# Payloadv04.net
KiCad netlist of a schematic drawn in EAGLE
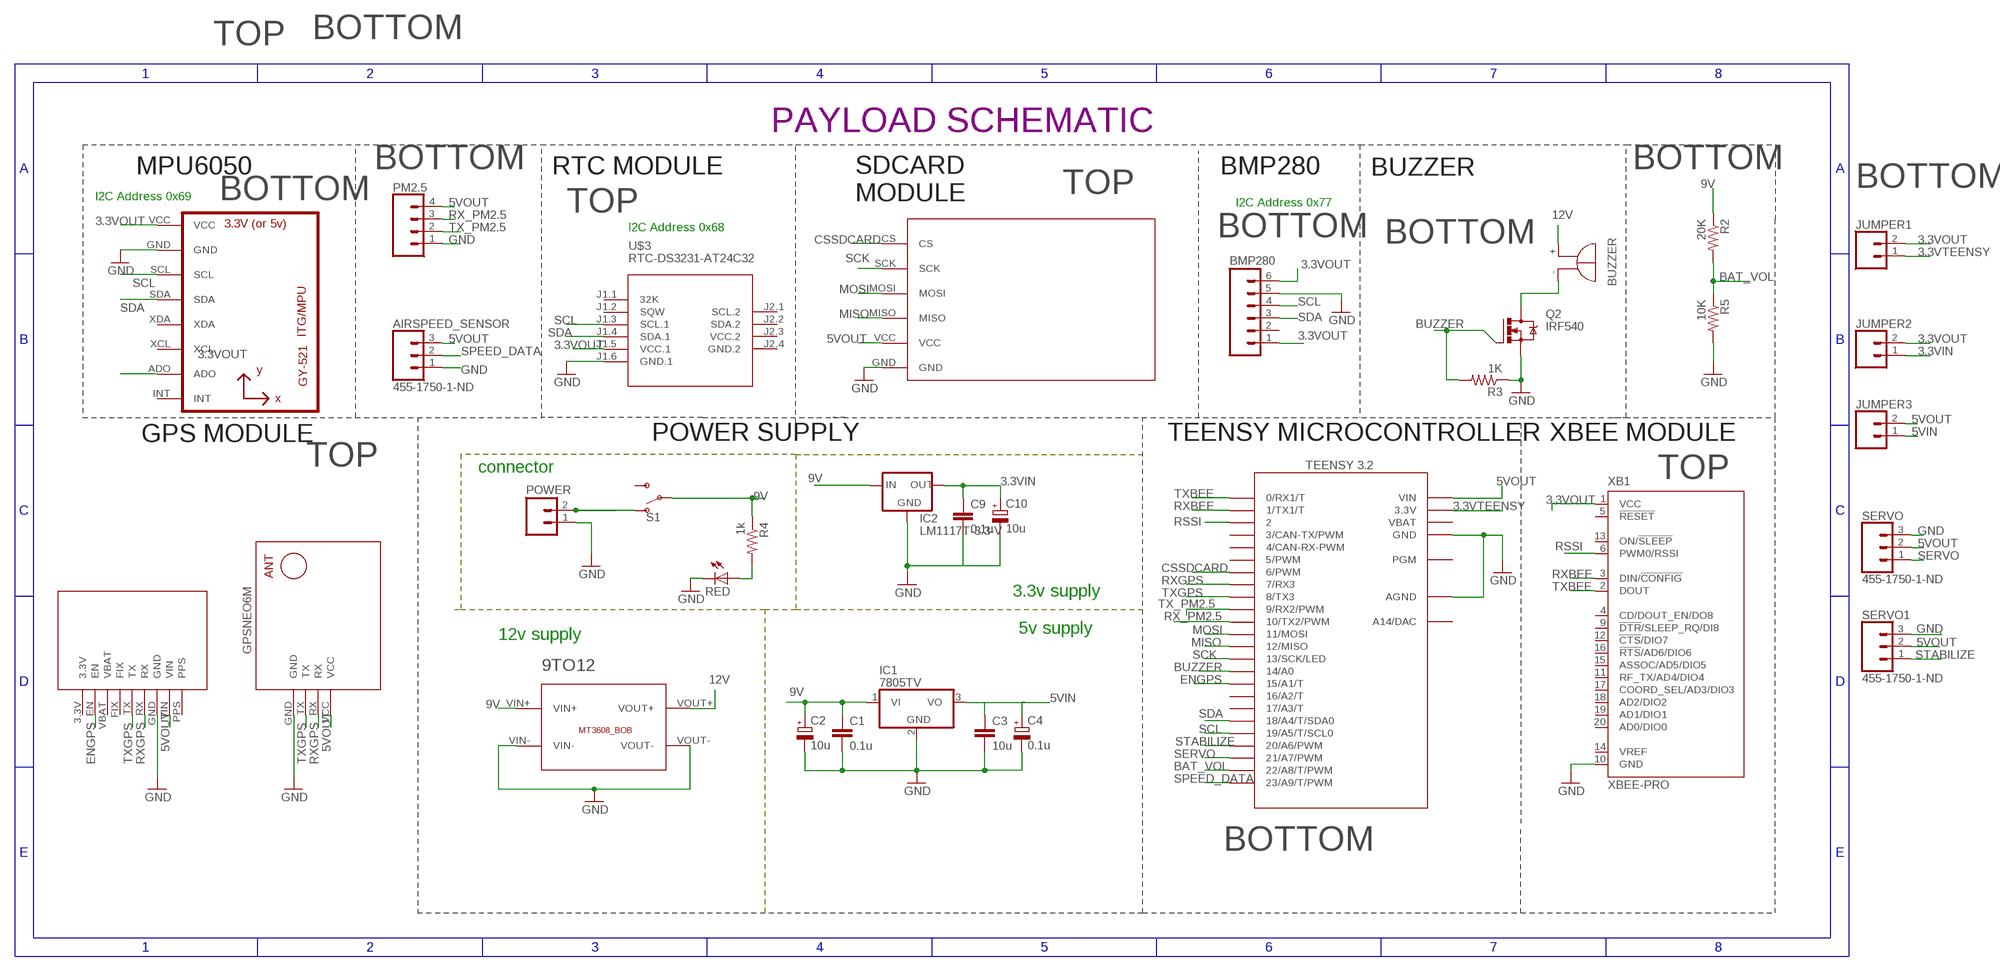
[diagram p0: schematic, sheet 1]

(export (version "E")
  (design (tool "Eeschema 10.0.6"))
  (components
    (comp (ref "9TO12")
      (value "BREAKOUTS_MT3608_BOB")
      (footprint "eagle-import:BREAKOUTS_MT3608_BOB")
      (libsource (lib "eagle-import") (part "BREAKOUTS_MT3608_BOB"))
    )
    (comp (ref "AIRSPEED_SENSOR")
      (value "455-1750-1-ND")
      (footprint "eagle-import:1X03")
      (libsource (lib "eagle-import") (part "CONN_03"))
    )
    (comp (ref "BMP280")
      (value "M06")
      (footprint "eagle-import:06P")
      (libsource (lib "eagle-import") (part "M06"))
    )
    (comp (ref "C1")
      (value "0.1u")
      (footprint "eagle-import:C025-025X050")
      (libsource (lib "eagle-import") (part "C-EU025-025X050"))
    )
    (comp (ref "C2")
      (value "10u")
      (footprint "eagle-import:E2,5-6")
      (libsource (lib "eagle-import") (part "CPOL-EUE2.5-6"))
    )
    (comp (ref "C3")
      (value "10u")
      (footprint "eagle-import:C025-025X050")
      (libsource (lib "eagle-import") (part "C-EU025-025X050"))
    )
    (comp (ref "C4")
      (value "0.1u")
      (footprint "eagle-import:E2,5-6")
      (libsource (lib "eagle-import") (part "CPOL-EUE2.5-6"))
    )
    (comp (ref "C9")
      (value "0.1u")
      (footprint "eagle-import:C025-025X050")
      (libsource (lib "eagle-import") (part "C-EU025-025X050"))
    )
    (comp (ref "C10")
      (value "10u")
      (footprint "eagle-import:E2,5-6")
      (libsource (lib "eagle-import") (part "CPOL-EUE2.5-6"))
    )
    (comp (ref "IC1")
      (value "7805TV")
      (footprint "eagle-import:TO220V")
      (libsource (lib "eagle-import") (part "78TV05"))
    )
    (comp (ref "IC2")
      (value "LM1117T-3.3-V")
      (footprint "eagle-import:TO220V")
      (libsource (lib "eagle-import") (part "LM1117T--V3.3"))
    )
    (comp (ref "JUMPER1")
      (value "CONN_02")
      (footprint "eagle-import:1X02")
      (libsource (lib "eagle-import") (part "CONN_02"))
    )
    (comp (ref "JUMPER2")
      (value "CONN_02")
      (footprint "eagle-import:1X02")
      (libsource (lib "eagle-import") (part "CONN_02"))
    )
    (comp (ref "JUMPER3")
      (value "CONN_02")
      (footprint "eagle-import:1X02")
      (libsource (lib "eagle-import") (part "CONN_02"))
    )
    (comp (ref "PM2.5")
      (value "CONN_04")
      (footprint "eagle-import:1X04")
      (libsource (lib "eagle-import") (part "CONN_04"))
    )
    (comp (ref "POWER")
      (value "CEDT_JANUARY_2015_V5_M02")
      (footprint "eagle-import:CEDT_JANUARY_2015_V5_02P")
      (libsource (lib "eagle-import") (part "CEDT_JANUARY_2015_V5_M02"))
    )
    (comp (ref "Q2")
      (value "IRF540")
      (footprint "eagle-import:TO220BV")
      (libsource (lib "eagle-import") (part "IRF540"))
    )
    (comp (ref "R2")
      (value "20K")
      (footprint "eagle-import:0204_7")
      (libsource (lib "eagle-import") (part "R-US_0204/7"))
    )
    (comp (ref "R3")
      (value "1K")
      (footprint "eagle-import:0204_7")
      (libsource (lib "eagle-import") (part "R-US_0204/7"))
    )
    (comp (ref "R4")
      (value "1k")
      (footprint "eagle-import:0204_7")
      (libsource (lib "eagle-import") (part "R-US_0204/7"))
    )
    (comp (ref "R5")
      (value "10K")
      (footprint "eagle-import:0204_7")
      (libsource (lib "eagle-import") (part "R-US_0204/7"))
    )
    (comp (ref "RED")
      (value "red")
      (footprint "eagle-import:LED3MM")
      (libsource (lib "eagle-import") (part "LED3MM"))
    )
    (comp (ref "S1")
      (value "SWITCH-SPDT-PTH-11.6X4.0MM")
      (footprint "eagle-import:SWITCH_SPDT_PTH_11.6X4.0MM")
      (libsource (lib "eagle-import") (part "SWITCH-SPDT-PTH-11.6X4.0MM"))
    )
    (comp (ref "SERVO")
      (value "455-1750-1-ND")
      (footprint "eagle-import:1X03")
      (libsource (lib "eagle-import") (part "CONN_03"))
    )
    (comp (ref "SERVO1")
      (value "455-1750-1-ND")
      (footprint "eagle-import:1X03")
      (libsource (lib "eagle-import") (part "CONN_03"))
    )
    (comp (ref "SG1")
      (value "BUZZER_EB2209A")
      (footprint "eagle-import:BUZZER_EB2209A")
      (libsource (lib "eagle-import") (part "BUZZER_EB2209A"))
    )
    (comp (ref "U$1")
      (value "GPS-RECEIVER-NEO6M")
      (footprint "eagle-import:GPS-RECEIVER-NEO6M")
      (libsource (lib "eagle-import") (part "GPS-RECEIVER-NEO6M"))
    )
    (comp (ref "U$2")
      (value "TEENSY_3.1-3.2_OUTER_ROW")
      (footprint "eagle-import:TEENSY_3.0-3.2&LC_OUTER_ROW")
      (libsource (lib "eagle-import") (part "TEENSY_3.1-3.2_OUTER_ROW"))
    )
    (comp (ref "U$3")
      (value "RTC-DS3231-AT24C32")
      (footprint "eagle-import:RTC-DS3231-AT24C32")
      (libsource (lib "eagle-import") (part "RTC-DS3231-AT24C32"))
    )
    (comp (ref "U$4")
      (value "ADAFRUIT_GPS")
      (footprint "eagle-import:ADAFRUIT_GPS")
      (libsource (lib "eagle-import") (part "ADAFRUIT_GPS"))
    )
    (comp (ref "U$5")
      (value "SDCARD")
      (footprint "eagle-import:M0SDCARDMODULE")
      (libsource (lib "eagle-import") (part "SDCARD"))
    )
    (comp (ref "U1")
      (value "GY-521MPU6050")
      (footprint "eagle-import:GY-521")
      (libsource (lib "eagle-import") (part "GY-521MPU6050"))
    )
    (comp (ref "XB1")
      (value "XBEE-PRO")
      (footprint "eagle-import:XBEE-PRO")
      (fields (field (name "MPN") "XBP24-AWI-001"))
      (libsource (lib "eagle-import") (part "XBEE-PRO"))
    )
  )
  (nets
    (net (code "1") (name "/3.3VIN") (class "Default")
      (node (ref "C10") (pin "+") (pinfunction "+_+") (pintype "passive"))
      (node (ref "C9") (pin "1") (pinfunction "1_1") (pintype "passive"))
      (node (ref "IC2") (pin "2") (pinfunction "OUT_2") (pintype "passive"))
      (node (ref "JUMPER2") (pin "1") (pinfunction "1_1") (pintype "passive"))
    )
    (net (code "2") (name "/3.3VOUT") (class "Default")
      (node (ref "BMP280") (pin "1") (pinfunction "1_1") (pintype "passive"))
      (node (ref "BMP280") (pin "6") (pinfunction "6_6") (pintype "passive"))
      (node (ref "JUMPER1") (pin "2") (pinfunction "2_2") (pintype "passive"))
      (node (ref "JUMPER2") (pin "2") (pinfunction "2_2") (pintype "passive"))
      (node (ref "U$3") (pin "J1.5") (pinfunction "VCC.1_J1.5") (pintype "power_in"))
      (node (ref "U1") (pin "ADO") (pinfunction "ADO_ADO") (pintype "bidirectional"))
      (node (ref "U1") (pin "VCC") (pinfunction "VCC_VCC") (pintype "bidirectional"))
      (node (ref "XB1") (pin "1") (pinfunction "VCC_1") (pintype "power_in"))
    )
    (net (code "3") (name "/3.3VTEENSY") (class "Default")
      (node (ref "JUMPER1") (pin "1") (pinfunction "1_1") (pintype "passive"))
      (node (ref "U$2") (pin "3.3V") (pinfunction "3.3V_3.3V") (pintype "power_in"))
      (node (ref "U$2") (pin "3.3V1") (pinfunction "3.3V_3.3V1") (pintype "power_in"))
    )
    (net (code "4") (name "/5VIN") (class "Default")
      (node (ref "C3") (pin "1") (pinfunction "1_1") (pintype "passive"))
      (node (ref "C4") (pin "+") (pinfunction "+_+") (pintype "passive"))
      (node (ref "IC1") (pin "3") (pinfunction "VO_3") (pintype "passive"))
      (node (ref "JUMPER3") (pin "1") (pinfunction "1_1") (pintype "passive"))
    )
    (net (code "5") (name "/5VOUT") (class "Default")
      (node (ref "AIRSPEED_SENSOR") (pin "3") (pinfunction "3_3") (pintype "passive"))
      (node (ref "JUMPER3") (pin "2") (pinfunction "2_2") (pintype "passive"))
      (node (ref "PM2.5") (pin "4") (pinfunction "4_4") (pintype "passive"))
      (node (ref "SERVO") (pin "2") (pinfunction "2_2") (pintype "passive"))
      (node (ref "SERVO1") (pin "2") (pinfunction "2_2") (pintype "passive"))
      (node (ref "U$1") (pin "VCC") (pinfunction "VCC_VCC") (pintype "power_in"))
      (node (ref "U$2") (pin "VIN") (pinfunction "VIN_VIN") (pintype "power_in"))
      (node (ref "U$4") (pin "VIN") (pinfunction "VIN_VIN") (pintype "bidirectional"))
      (node (ref "U$5") (pin "VCC") (pinfunction "VCC_VCC") (pintype "bidirectional"))
    )
    (net (code "6") (name "/9V") (class "Default")
      (node (ref "9TO12") (pin "VIN+") (pinfunction "VIN+_VIN+") (pintype "bidirectional"))
      (node (ref "C1") (pin "1") (pinfunction "1_1") (pintype "passive"))
      (node (ref "C2") (pin "+") (pinfunction "+_+") (pintype "passive"))
      (node (ref "IC1") (pin "1") (pinfunction "VI_1") (pintype "input"))
      (node (ref "IC2") (pin "3") (pinfunction "IN_3") (pintype "input"))
      (node (ref "R2") (pin "1") (pinfunction "1_1") (pintype "passive"))
      (node (ref "R4") (pin "1") (pinfunction "1_1") (pintype "passive"))
      (node (ref "S1") (pin "2") (pinfunction "P_2") (pintype "passive"))
    )
    (net (code "7") (name "/12V") (class "Default")
      (node (ref "9TO12") (pin "VOUT+") (pinfunction "VOUT+_VOUT+") (pintype "bidirectional"))
      (node (ref "SG1") (pin "+") (pinfunction "+_+") (pintype "passive"))
    )
    (net (code "8") (name "/BAT_VOL") (class "Default")
      (node (ref "R2") (pin "2") (pinfunction "2_2") (pintype "passive"))
      (node (ref "R5") (pin "1") (pinfunction "1_1") (pintype "passive"))
      (node (ref "U$2") (pin "22/A8") (pinfunction "22/A8/T/PWM_22/A8") (pintype "bidirectional"))
    )
    (net (code "9") (name "/BUZZER") (class "Default")
      (node (ref "Q2") (pin "G") (pinfunction "G_G") (pintype "passive"))
      (node (ref "R3") (pin "2") (pinfunction "2_2") (pintype "passive"))
      (node (ref "U$2") (pin "14/A0") (pinfunction "14/A0_14/A0") (pintype "bidirectional"))
    )
    (net (code "10") (name "/CSSDCARD") (class "Default")
      (node (ref "U$2") (pin "6") (pinfunction "6/PWM_6") (pintype "bidirectional"))
      (node (ref "U$5") (pin "CS") (pinfunction "CS_CS") (pintype "bidirectional"))
    )
    (net (code "11") (name "/ENGPS") (class "Default")
      (node (ref "U$2") (pin "15/A1") (pinfunction "15/A1/T_15/A1") (pintype "bidirectional"))
      (node (ref "U$4") (pin "EN") (pinfunction "EN_EN") (pintype "bidirectional"))
    )
    (net (code "12") (name "/GND.2") (class "Default")
      (node (ref "U$3") (pin "J2.4") (pinfunction "GND.2_J2.4") (pintype "power_in"))
    )
    (net (code "13") (name "/MISO") (class "Default")
      (node (ref "U$2") (pin "12") (pinfunction "12/MISO_12") (pintype "bidirectional"))
      (node (ref "U$5") (pin "MISO") (pinfunction "MISO_MISO") (pintype "bidirectional"))
    )
    (net (code "14") (name "/MOSI") (class "Default")
      (node (ref "U$2") (pin "11") (pinfunction "11/MOSI_11") (pintype "bidirectional"))
      (node (ref "U$5") (pin "MOSI") (pinfunction "MOSI_MOSI") (pintype "bidirectional"))
    )
    (net (code "15") (name "/RSSI") (class "Default")
      (node (ref "U$2") (pin "2") (pinfunction "2_2") (pintype "bidirectional"))
      (node (ref "XB1") (pin "6") (pinfunction "PWM0/RSSI_6") (pintype "output"))
    )
    (net (code "16") (name "/RXBEE") (class "Default")
      (node (ref "U$2") (pin "1") (pinfunction "1/TX1/T_1") (pintype "bidirectional"))
      (node (ref "XB1") (pin "3") (pinfunction "DIN/~{CONFIG}_3") (pintype "input"))
    )
    (net (code "17") (name "/RXGPS") (class "Default")
      (node (ref "U$1") (pin "RX") (pinfunction "RX_RX") (pintype "bidirectional"))
      (node (ref "U$2") (pin "7") (pinfunction "7/RX3_7") (pintype "bidirectional"))
      (node (ref "U$4") (pin "RX") (pinfunction "RX_RX") (pintype "bidirectional"))
    )
    (net (code "18") (name "/RX_PM2.5") (class "Default")
      (node (ref "PM2.5") (pin "3") (pinfunction "3_3") (pintype "passive"))
      (node (ref "U$2") (pin "10") (pinfunction "10/TX2/PWM_10") (pintype "bidirectional"))
    )
    (net (code "19") (name "/SCK") (class "Default")
      (node (ref "U$2") (pin "13") (pinfunction "13/SCK/LED_13") (pintype "bidirectional"))
      (node (ref "U$5") (pin "SCK") (pinfunction "SCK_SCK") (pintype "bidirectional"))
    )
    (net (code "20") (name "/SCL") (class "Default")
      (node (ref "BMP280") (pin "4") (pinfunction "4_4") (pintype "passive"))
      (node (ref "U$2") (pin "19/A5") (pinfunction "19/A5/T/SCL0_19/A5") (pintype "bidirectional"))
      (node (ref "U$3") (pin "J1.3") (pinfunction "SCL.1_J1.3") (pintype "bidirectional"))
      (node (ref "U1") (pin "SCL") (pinfunction "SCL_SCL") (pintype "bidirectional"))
    )
    (net (code "21") (name "/SDA") (class "Default")
      (node (ref "BMP280") (pin "3") (pinfunction "3_3") (pintype "passive"))
      (node (ref "U$2") (pin "18/A4") (pinfunction "18/A4/T/SDA0_18/A4") (pintype "bidirectional"))
      (node (ref "U$3") (pin "J1.4") (pinfunction "SDA.1_J1.4") (pintype "bidirectional"))
      (node (ref "U1") (pin "SDA") (pinfunction "SDA_SDA") (pintype "bidirectional"))
    )
    (net (code "22") (name "/SERVO") (class "Default")
      (node (ref "SERVO") (pin "1") (pinfunction "1_1") (pintype "passive"))
      (node (ref "U$2") (pin "21/A7") (pinfunction "21/A7/PWM_21/A7") (pintype "bidirectional"))
    )
    (net (code "23") (name "/SPEED_DATA") (class "Default")
      (node (ref "AIRSPEED_SENSOR") (pin "2") (pinfunction "2_2") (pintype "passive"))
      (node (ref "U$2") (pin "23/A9") (pinfunction "23/A9/T/PWM_23/A9") (pintype "bidirectional"))
    )
    (net (code "24") (name "/STABILIZE") (class "Default")
      (node (ref "SERVO1") (pin "1") (pinfunction "1_1") (pintype "passive"))
      (node (ref "U$2") (pin "20/A6") (pinfunction "20/A6/PWM_20/A6") (pintype "bidirectional"))
    )
    (net (code "25") (name "/TXBEE") (class "Default")
      (node (ref "U$2") (pin "0") (pinfunction "0/RX1/T_0") (pintype "bidirectional"))
      (node (ref "XB1") (pin "2") (pinfunction "DOUT_2") (pintype "output"))
    )
    (net (code "26") (name "/TXGPS") (class "Default")
      (node (ref "U$1") (pin "TX") (pinfunction "TX_TX") (pintype "bidirectional"))
      (node (ref "U$2") (pin "8") (pinfunction "8/TX3_8") (pintype "bidirectional"))
      (node (ref "U$4") (pin "TX") (pinfunction "TX_TX") (pintype "bidirectional"))
    )
    (net (code "27") (name "/TX_PM2.5") (class "Default")
      (node (ref "PM2.5") (pin "2") (pinfunction "2_2") (pintype "passive"))
      (node (ref "U$2") (pin "9") (pinfunction "9/RX2/PWM_9") (pintype "bidirectional"))
    )
    (net (code "28") (name "/VBAT") (class "Default")
      (node (ref "U$2") (pin "VBAT") (pinfunction "VBAT_VBAT") (pintype "power_in"))
    )
    (net (code "29") (name "/VCC.2") (class "Default")
      (node (ref "U$3") (pin "J2.3") (pinfunction "VCC.2_J2.3") (pintype "power_in"))
    )
    (net (code "30") (name "GND") (class "Default")
      (node (ref "9TO12") (pin "VIN-") (pinfunction "VIN-_VIN-") (pintype "bidirectional"))
      (node (ref "9TO12") (pin "VOUT-") (pinfunction "VOUT-_VOUT-") (pintype "bidirectional"))
      (node (ref "AIRSPEED_SENSOR") (pin "1") (pinfunction "1_1") (pintype "passive"))
      (node (ref "BMP280") (pin "5") (pinfunction "5_5") (pintype "passive"))
      (node (ref "C1") (pin "2") (pinfunction "2_2") (pintype "passive"))
      (node (ref "C10") (pin "-") (pinfunction "-_-") (pintype "passive"))
      (node (ref "C2") (pin "-") (pinfunction "-_-") (pintype "passive"))
      (node (ref "C3") (pin "2") (pinfunction "2_2") (pintype "passive"))
      (node (ref "C4") (pin "-") (pinfunction "-_-") (pintype "passive"))
      (node (ref "C9") (pin "2") (pinfunction "2_2") (pintype "passive"))
      (node (ref "IC1") (pin "2") (pinfunction "GND_2") (pintype "passive"))
      (node (ref "IC2") (pin "1") (pinfunction "GND_1") (pintype "input"))
      (node (ref "PM2.5") (pin "1") (pinfunction "1_1") (pintype "passive"))
      (node (ref "POWER") (pin "1") (pinfunction "1_1") (pintype "passive"))
      (node (ref "Q2") (pin "S") (pinfunction "S_S") (pintype "passive"))
      (node (ref "R3") (pin "1") (pinfunction "1_1") (pintype "passive"))
      (node (ref "R5") (pin "2") (pinfunction "2_2") (pintype "passive"))
      (node (ref "RED") (pin "K") (pinfunction "C_K") (pintype "passive"))
      (node (ref "SERVO") (pin "3") (pinfunction "3_3") (pintype "passive"))
      (node (ref "SERVO1") (pin "3") (pinfunction "3_3") (pintype "passive"))
      (node (ref "U$1") (pin "GND") (pinfunction "GND_GND") (pintype "bidirectional"))
      (node (ref "U$2") (pin "AGND") (pinfunction "AGND_AGND") (pintype "power_in"))
      (node (ref "U$2") (pin "GND") (pinfunction "GND_GND") (pintype "power_in"))
      (node (ref "U$2") (pin "GND1") (pinfunction "GND_GND1") (pintype "power_in"))
      (node (ref "U$3") (pin "J1.6") (pinfunction "GND.1_J1.6") (pintype "power_in"))
      (node (ref "U$4") (pin "GND") (pinfunction "GND_GND") (pintype "bidirectional"))
      (node (ref "U$5") (pin "GND") (pinfunction "GND_GND") (pintype "bidirectional"))
      (node (ref "U1") (pin "GND") (pinfunction "GND_GND") (pintype "bidirectional"))
      (node (ref "XB1") (pin "10") (pinfunction "GND_10") (pintype "power_in"))
    )
    (net (code "31") (name "Net-(Q2-PadD)") (class "Default")
      (node (ref "Q2") (pin "D") (pinfunction "D_D") (pintype "passive"))
      (node (ref "SG1") (pin "-") (pinfunction "-_-") (pintype "passive"))
    )
    (net (code "32") (name "Net-(R4-Pad2)") (class "Default")
      (node (ref "R4") (pin "2") (pinfunction "2_2") (pintype "passive"))
      (node (ref "RED") (pin "A") (pinfunction "A_A") (pintype "passive"))
    )
    (net (code "33") (name "Net-(S1-O)") (class "Default")
      (node (ref "POWER") (pin "2") (pinfunction "2_2") (pintype "passive"))
      (node (ref "S1") (pin "1") (pinfunction "O_1") (pintype "passive"))
    )
    (net (code "34") (name "unconnected-(BMP280-Pad2)") (class "Default")
      (node (ref "BMP280") (pin "2") (pinfunction "2_2") (pintype "passive"))
    )
    (net (code "35") (name "unconnected-(S1-S-Pad3)") (class "Default")
      (node (ref "S1") (pin "3") (pinfunction "S_3") (pintype "passive"))
    )
    (net (code "36") (name "unconnected-(U$2-3{slash}CAN-TX{slash}PWM-Pad3)") (class "Default")
      (node (ref "U$2") (pin "3") (pinfunction "3/CAN-TX/PWM_3") (pintype "bidirectional"))
    )
    (net (code "37") (name "unconnected-(U$2-4{slash}CAN-RX-PWM-Pad4)") (class "Default")
      (node (ref "U$2") (pin "4") (pinfunction "4/CAN-RX-PWM_4") (pintype "bidirectional"))
    )
    (net (code "38") (name "unconnected-(U$2-5{slash}PWM-Pad5)") (class "Default")
      (node (ref "U$2") (pin "5") (pinfunction "5/PWM_5") (pintype "bidirectional"))
    )
    (net (code "39") (name "unconnected-(U$2-16{slash}A2{slash}T-Pad16{slash}A2)") (class "Default")
      (node (ref "U$2") (pin "16/A2") (pinfunction "16/A2/T_16/A2") (pintype "bidirectional"))
    )
    (net (code "40") (name "unconnected-(U$2-17{slash}A3{slash}T-Pad17{slash}A3)") (class "Default")
      (node (ref "U$2") (pin "17/A3") (pinfunction "17/A3/T_17/A3") (pintype "bidirectional"))
    )
    (net (code "41") (name "unconnected-(U$2-A14{slash}DAC-PadRESET{slash}DAC)") (class "Default")
      (node (ref "U$2") (pin "RESET/DAC") (pinfunction "A14/DAC_RESET/DAC") (pintype "bidirectional"))
    )
    (net (code "42") (name "unconnected-(U$2-PadPGM)") (class "Default")
      (node (ref "U$2") (pin "PGM") (pinfunction "PGM_PGM") (pintype "bidirectional"))
    )
    (net (code "43") (name "unconnected-(U$3-32K-PadJ1.1)") (class "Default")
      (node (ref "U$3") (pin "J1.1") (pinfunction "32K_J1.1") (pintype "bidirectional"))
    )
    (net (code "44") (name "unconnected-(U$3-SCL.2-PadJ2.1)") (class "Default")
      (node (ref "U$3") (pin "J2.1") (pinfunction "SCL.2_J2.1") (pintype "bidirectional"))
    )
    (net (code "45") (name "unconnected-(U$3-SDA.2-PadJ2.2)") (class "Default")
      (node (ref "U$3") (pin "J2.2") (pinfunction "SDA.2_J2.2") (pintype "bidirectional"))
    )
    (net (code "46") (name "unconnected-(U$3-SQW-PadJ1.2)") (class "Default")
      (node (ref "U$3") (pin "J1.2") (pinfunction "SQW_J1.2") (pintype "bidirectional"))
    )
    (net (code "47") (name "unconnected-(U$4-Pad3.3V)") (class "Default")
      (node (ref "U$4") (pin "3.3V") (pinfunction "3.3V_3.3V") (pintype "bidirectional"))
    )
    (net (code "48") (name "unconnected-(U$4-PadFIX)") (class "Default")
      (node (ref "U$4") (pin "FIX") (pinfunction "FIX_FIX") (pintype "bidirectional"))
    )
    (net (code "49") (name "unconnected-(U$4-PadPPS)") (class "Default")
      (node (ref "U$4") (pin "PPS") (pinfunction "PPS_PPS") (pintype "bidirectional"))
    )
    (net (code "50") (name "unconnected-(U$4-PadVBAT)") (class "Default")
      (node (ref "U$4") (pin "VBAT") (pinfunction "VBAT_VBAT") (pintype "bidirectional"))
    )
    (net (code "51") (name "unconnected-(U1-PadINT)") (class "Default")
      (node (ref "U1") (pin "INT") (pinfunction "INT_INT") (pintype "bidirectional"))
    )
    (net (code "52") (name "unconnected-(U1-PadXCL)") (class "Default")
      (node (ref "U1") (pin "XCL") (pinfunction "XCL_XCL") (pintype "bidirectional"))
    )
    (net (code "53") (name "unconnected-(U1-PadXDA)") (class "Default")
      (node (ref "U1") (pin "XDA") (pinfunction "XDA_XDA") (pintype "bidirectional"))
    )
    (net (code "54") (name "unconnected-(XB1-AD0{slash}DIO0-Pad20)") (class "Default")
      (node (ref "XB1") (pin "20") (pinfunction "AD0/DIO0_20") (pintype "bidirectional"))
    )
    (net (code "55") (name "unconnected-(XB1-AD1{slash}DIO1-Pad19)") (class "Default")
      (node (ref "XB1") (pin "19") (pinfunction "AD1/DIO1_19") (pintype "bidirectional"))
    )
    (net (code "56") (name "unconnected-(XB1-AD2{slash}DIO2-Pad18)") (class "Default")
      (node (ref "XB1") (pin "18") (pinfunction "AD2/DIO2_18") (pintype "bidirectional"))
    )
    (net (code "57") (name "unconnected-(XB1-ASSOC{slash}AD5{slash}DIO5-Pad15)") (class "Default")
      (node (ref "XB1") (pin "15") (pinfunction "ASSOC/AD5/DIO5_15") (pintype "bidirectional"))
    )
    (net (code "58") (name "unconnected-(XB1-CD{slash}DOUT_EN{slash}DO8-Pad4)") (class "Default")
      (node (ref "XB1") (pin "4") (pinfunction "CD/DOUT_EN/DO8_4") (pintype "output"))
    )
    (net (code "59") (name "unconnected-(XB1-COORD_SEL{slash}AD3{slash}DIO3-Pad17)") (class "Default")
      (node (ref "XB1") (pin "17") (pinfunction "COORD_SEL/AD3/DIO3_17") (pintype "bidirectional"))
    )
    (net (code "60") (name "unconnected-(XB1-ON{slash}~{SLEEP}-Pad13)") (class "Default")
      (node (ref "XB1") (pin "13") (pinfunction "ON/~{SLEEP}_13") (pintype "output"))
    )
    (net (code "61") (name "unconnected-(XB1-RF_TX{slash}AD4{slash}DIO4-Pad11)") (class "Default")
      (node (ref "XB1") (pin "11") (pinfunction "RF_TX/AD4/DIO4_11") (pintype "bidirectional"))
    )
    (net (code "62") (name "unconnected-(XB1-VREF-Pad14)") (class "Default")
      (node (ref "XB1") (pin "14") (pinfunction "VREF_14") (pintype "input"))
    )
    (net (code "63") (name "unconnected-(XB1-~{CTS}{slash}DIO7-Pad12)") (class "Default")
      (node (ref "XB1") (pin "12") (pinfunction "~{CTS}/DIO7_12") (pintype "bidirectional"))
    )
    (net (code "64") (name "unconnected-(XB1-~{DTR}{slash}SLEEP_RQ{slash}DI8-Pad9)") (class "Default")
      (node (ref "XB1") (pin "9") (pinfunction "~{DTR}/SLEEP_RQ/DI8_9") (pintype "bidirectional"))
    )
    (net (code "65") (name "unconnected-(XB1-~{RESET}-Pad5)") (class "Default")
      (node (ref "XB1") (pin "5") (pinfunction "~{RESET}_5") (pintype "input"))
    )
    (net (code "66") (name "unconnected-(XB1-~{RTS}{slash}AD6{slash}DIO6-Pad16)") (class "Default")
      (node (ref "XB1") (pin "16") (pinfunction "~{RTS}/AD6/DIO6_16") (pintype "bidirectional"))
    )
  )
)
